# power.net
KiCad netlist of a schematic drawn in Altium Designer
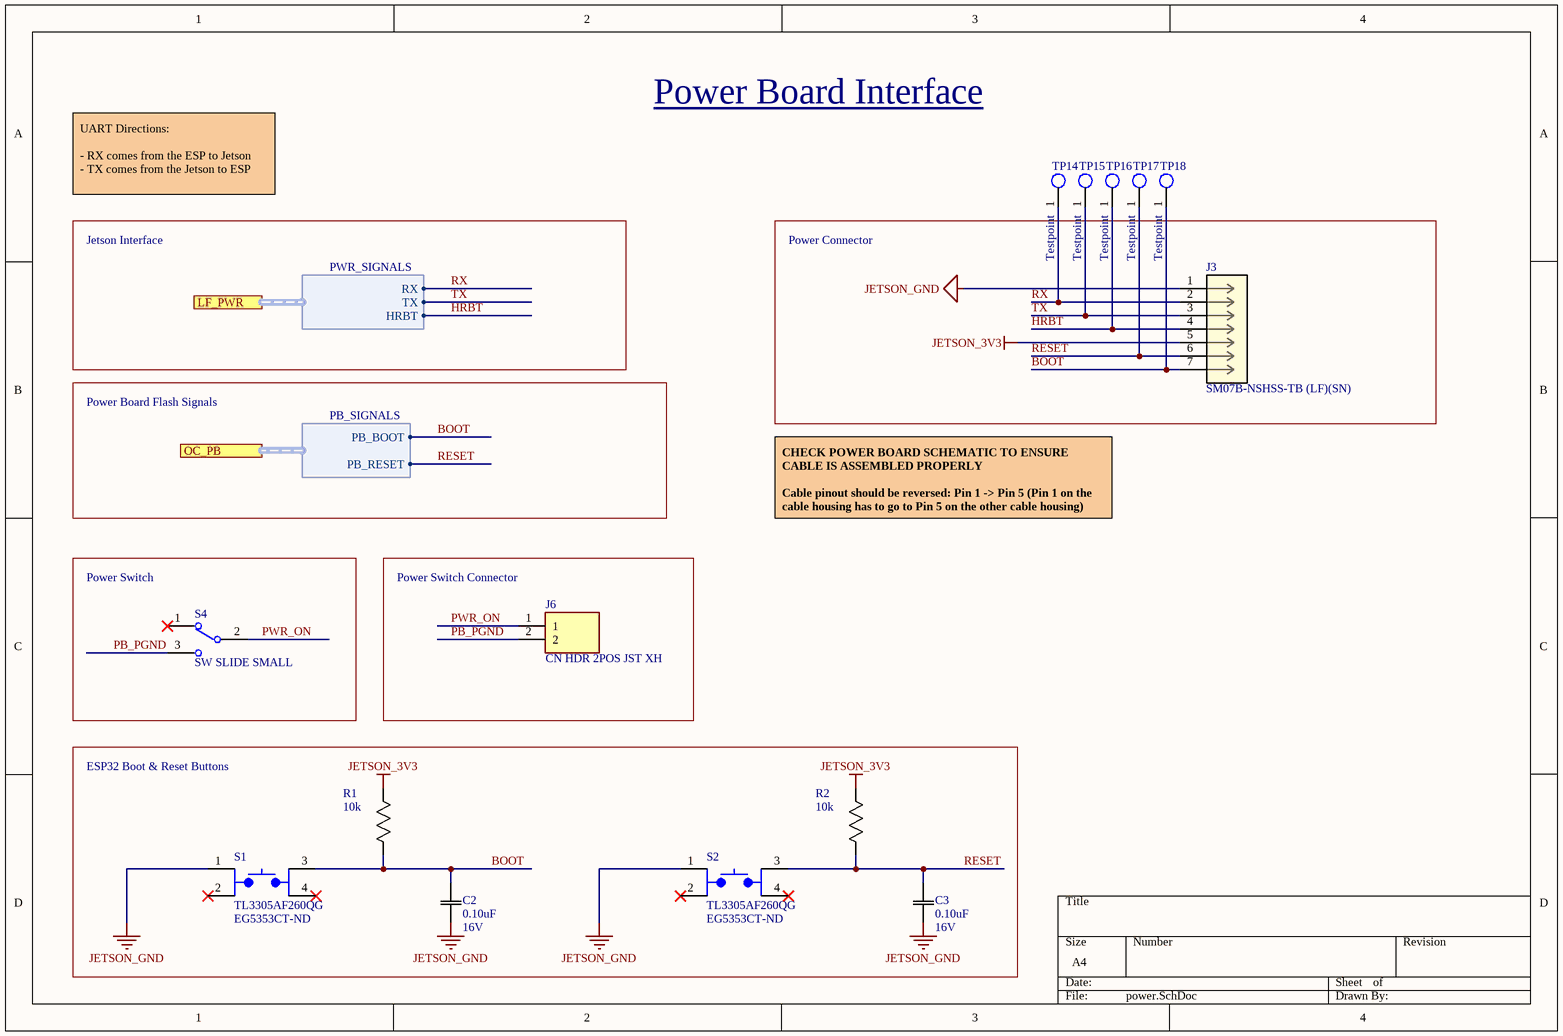
[diagram p0: power.SchDoc]

(export (version "E")
  (design (tool "Eeschema 10.0.6"))
  (components
    (comp (ref "C2")
      (value "0.10uF")
      (footprint "0603")
      (description "CAP CER 0.10UF 16V X5R 0603")
      (fields
        (field (name "TOLERANCE") "10%")
        (field (name "RATING") "16V")
        (field (name "PART NUMBER") "CAP 0.10uF 16V")
      )
      (libsource (lib "capacitor_library") (part "CAP 0.10uF 16V"))
    )
    (comp (ref "C3")
      (value "0.10uF")
      (footprint "0603")
      (description "CAP CER 0.10UF 16V X5R 0603")
      (fields
        (field (name "TOLERANCE") "10%")
        (field (name "RATING") "16V")
        (field (name "PART NUMBER") "CAP 0.10uF 16V")
      )
      (libsource (lib "capacitor_library") (part "CAP 0.10uF 16V"))
    )
    (comp (ref "J3")
      (value "SM07B-NSHSS-TB (LF)(SN)")
      (footprint "JST_SM07B-NSHSS-TB_(LF)(SN)")
      (description "Connector Header Surface Mount, Right Angle 7 position 0.039\" (1.00mm)")
      (fields (field (name "MP") "SM12B-NSHSS-TB (LF)(SN)") (field (name "MF") "JST Sales America Inc."))
      (libsource (lib "Connector_Library") (part "CN 7POS JST NSH SMT RA"))
    )
    (comp (ref "J6")
      (value "CN HDR 2POS JST XH")
      (footprint "JST_B2B-XH-A(LF)(SN)")
      (description "Connector Header Through Hole 2 position 0.098 _2.50mm_\r\nJST XH")
      (fields (field (name "MP") "B2B-XH-A_LF__SN_") (field (name "MF") "JST Sales"))
      (libsource (lib "Connector_Library") (part "CN HDR 2POS JST XH"))
    )
    (comp (ref "R1")
      (value "10k")
      (footprint "0603")
      (description "RES SMD 10K OHM 5% 1/8W 0805")
      (fields (field (name "TOLERANCE") "5%") (field (name "PART NUMBER") "RES 10k 1/8W - 5%"))
      (libsource (lib "Resistor_Library") (part "RES 10k 1/8W 5%"))
    )
    (comp (ref "R2")
      (value "10k")
      (footprint "0603")
      (description "RES SMD 10K OHM 5% 1/8W 0805")
      (fields (field (name "TOLERANCE") "5%") (field (name "PART NUMBER") "RES 10k 1/8W - 5%"))
      (libsource (lib "Resistor_Library") (part "RES 10k 1/8W 5%"))
    )
    (comp (ref "S1")
      (value "TL3305AF260QG")
      (footprint "SW_TL3305AF260QG")
      (description "Tactile Switch SPST-NO Top Actuated Surface Mount")
      (fields
        (field (name "MF") "E-Switch")
        (field (name "SUPPLIER PART NUMBER 1") "EG5353CT-ND")
        (field (name "PART NUMBER") "SW PUSH SMD")
      )
      (libsource (lib "Switch_Library") (part "SW PUSH SMD"))
    )
    (comp (ref "S2")
      (value "TL3305AF260QG")
      (footprint "SW_TL3305AF260QG")
      (description "Tactile Switch SPST-NO Top Actuated Surface Mount")
      (fields
        (field (name "MF") "E-Switch")
        (field (name "SUPPLIER PART NUMBER 1") "EG5353CT-ND")
        (field (name "PART NUMBER") "SW PUSH SMD")
      )
      (libsource (lib "Switch_Library") (part "SW PUSH SMD"))
    )
    (comp (ref "S4")
      (value "SW SLIDE SMALL")
      (footprint "SW SLIDE SMALL")
      (description "Slide Switch SPDT Surface Mount, Right Angle")
      (fields (field (name "MF") "C&K") (field (name "MP") "JS102011SAQN"))
      (libsource (lib "Switch_Library") (part "SW SLIDE SMALL"))
    )
    (comp (ref "TP14")
      (value "Testpoint")
      (footprint "TP_1mm")
      (fields (field (name "PART NUMBER") "TP_1MM"))
      (libsource (lib "Connector_Library") (part "Testpoint"))
    )
    (comp (ref "TP15")
      (value "Testpoint")
      (footprint "TP_1mm")
      (fields (field (name "PART NUMBER") "TP_1MM"))
      (libsource (lib "Connector_Library") (part "Testpoint"))
    )
    (comp (ref "TP16")
      (value "Testpoint")
      (footprint "TP_1mm")
      (fields (field (name "PART NUMBER") "TP_1MM"))
      (libsource (lib "Connector_Library") (part "Testpoint"))
    )
    (comp (ref "TP17")
      (value "Testpoint")
      (footprint "TP_1mm")
      (fields (field (name "PART NUMBER") "TP_1MM"))
      (libsource (lib "Connector_Library") (part "Testpoint"))
    )
    (comp (ref "TP18")
      (value "Testpoint")
      (footprint "TP_1mm")
      (fields (field (name "PART NUMBER") "TP_1MM"))
      (libsource (lib "Connector_Library") (part "Testpoint"))
    )
  )
  (nets
    (net (code "4") (name "/BOOT") (class "Default")
      (node (ref "C2") (pin "2") (pinfunction "C2_2") (pintype "passive"))
      (node (ref "J3") (pin "7") (pinfunction "7_7") (pintype "passive"))
      (node (ref "R1") (pin "2") (pinfunction "R2_2") (pintype "passive"))
      (node (ref "S1") (pin "3") (pinfunction "3_3") (pintype "passive"))
      (node (ref "TP18") (pin "1") (pinfunction "TP_1") (pintype "passive"))
    )
    (net (code "5") (name "/HRBT") (class "Default")
      (node (ref "J3") (pin "4") (pinfunction "4_4") (pintype "passive"))
      (node (ref "TP16") (pin "1") (pinfunction "TP_1") (pintype "passive"))
    )
    (net (code "6") (name "/PB_PGND") (class "Default")
      (node (ref "J6") (pin "2") (pinfunction "2_2") (pintype "passive"))
      (node (ref "S4") (pin "3") (pinfunction "3_3") (pintype "passive"))
    )
    (net (code "7") (name "/PWR_ON") (class "Default")
      (node (ref "J6") (pin "1") (pinfunction "1_1") (pintype "passive"))
      (node (ref "S4") (pin "2") (pinfunction "2_2") (pintype "passive"))
    )
    (net (code "8") (name "/RESET") (class "Default")
      (node (ref "C3") (pin "2") (pinfunction "C2_2") (pintype "passive"))
      (node (ref "J3") (pin "6") (pinfunction "6_6") (pintype "passive"))
      (node (ref "R2") (pin "2") (pinfunction "R2_2") (pintype "passive"))
      (node (ref "S2") (pin "3") (pinfunction "3_3") (pintype "passive"))
      (node (ref "TP17") (pin "1") (pinfunction "TP_1") (pintype "passive"))
    )
    (net (code "9") (name "/RX") (class "Default")
      (node (ref "J3") (pin "2") (pinfunction "2_2") (pintype "passive"))
      (node (ref "TP14") (pin "1") (pinfunction "TP_1") (pintype "passive"))
    )
    (net (code "10") (name "/TX") (class "Default")
      (node (ref "J3") (pin "3") (pinfunction "3_3") (pintype "passive"))
      (node (ref "TP15") (pin "1") (pinfunction "TP_1") (pintype "passive"))
    )
    (net (code "13") (name "JETSON_3V3") (class "Default")
      (node (ref "J3") (pin "5") (pinfunction "5_5") (pintype "passive"))
      (node (ref "R1") (pin "1") (pinfunction "R1_1") (pintype "passive"))
      (node (ref "R2") (pin "1") (pinfunction "R1_1") (pintype "passive"))
    )
    (net (code "14") (name "JETSON_GND") (class "Default")
      (node (ref "C2") (pin "1") (pinfunction "C1_1") (pintype "passive"))
      (node (ref "C3") (pin "1") (pinfunction "C1_1") (pintype "passive"))
      (node (ref "J3") (pin "1") (pinfunction "1_1") (pintype "passive"))
      (node (ref "S1") (pin "1") (pinfunction "1_1") (pintype "passive"))
      (node (ref "S2") (pin "1") (pinfunction "1_1") (pintype "passive"))
    )
    (net (code "15") (name "unconnected-(S1-Pad2)") (class "Default")
      (node (ref "S1") (pin "2") (pinfunction "2_2") (pintype "passive+no_connect"))
    )
    (net (code "16") (name "unconnected-(S1-Pad4)") (class "Default")
      (node (ref "S1") (pin "4") (pinfunction "4_4") (pintype "passive+no_connect"))
    )
    (net (code "17") (name "unconnected-(S2-Pad2)") (class "Default")
      (node (ref "S2") (pin "2") (pinfunction "2_2") (pintype "passive+no_connect"))
    )
    (net (code "18") (name "unconnected-(S2-Pad4)") (class "Default")
      (node (ref "S2") (pin "4") (pinfunction "4_4") (pintype "passive+no_connect"))
    )
    (net (code "19") (name "unconnected-(S4-Pad1)") (class "Default")
      (node (ref "S4") (pin "1") (pinfunction "1_1") (pintype "passive+no_connect"))
    )
  )
)
